# DCS.net
KiCad netlist of a schematic drawn in EAGLE
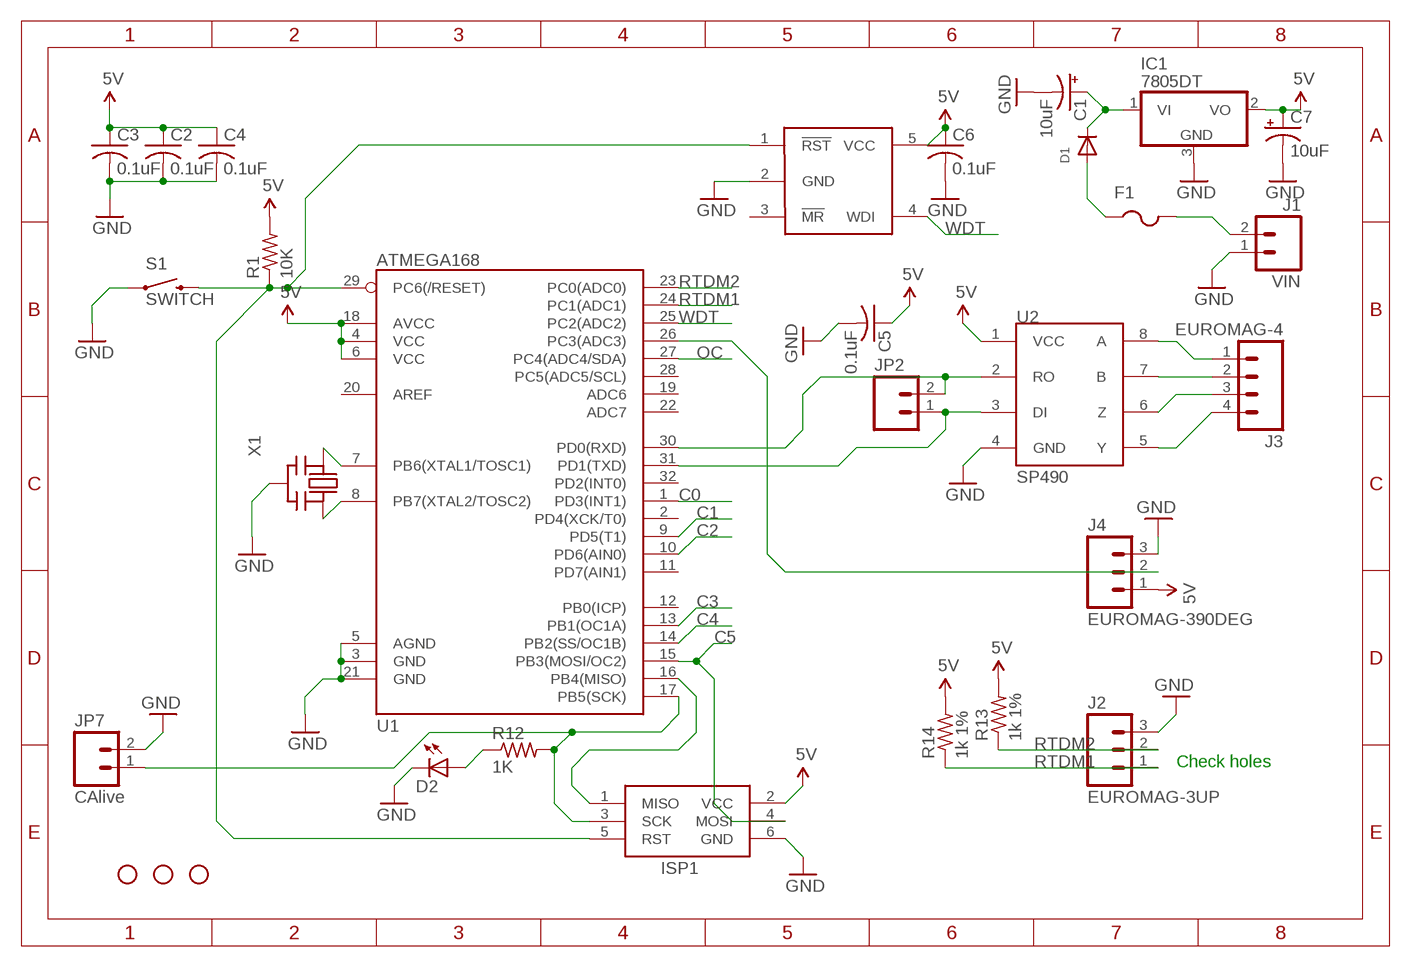
[diagram p0: schematic, sheet 1]
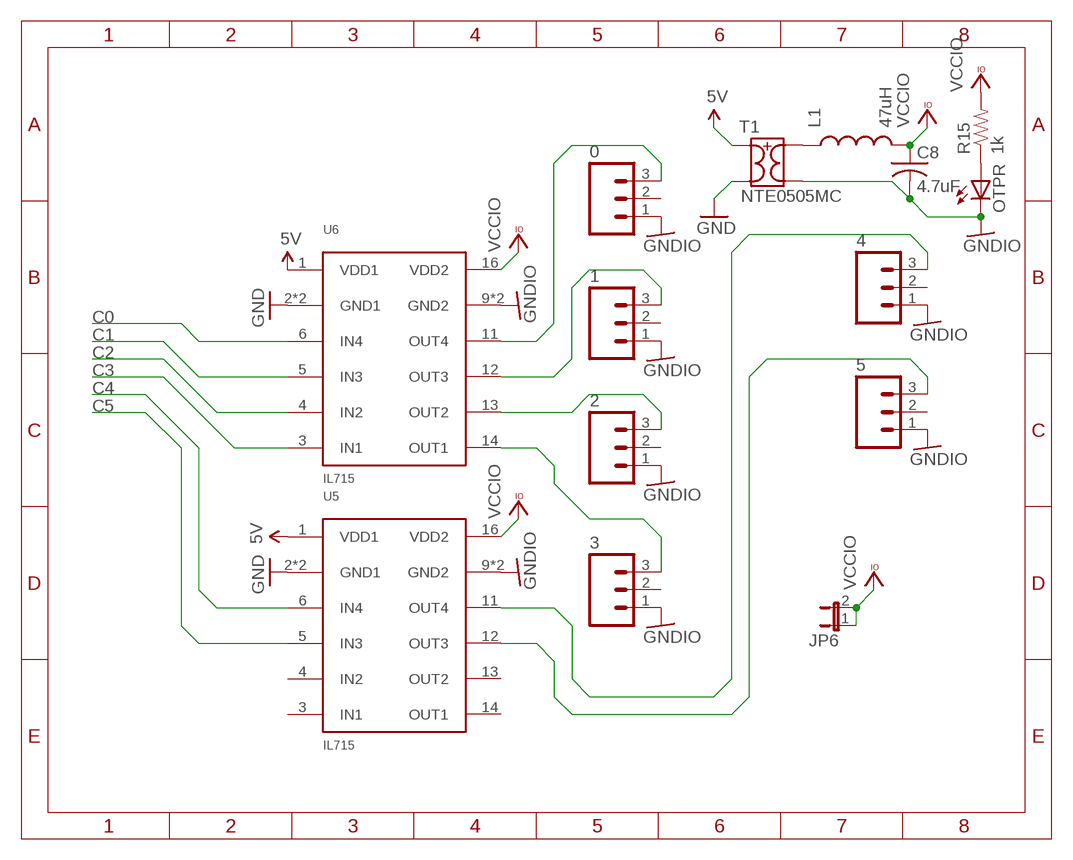
[diagram p1: schematic, sheet 2]
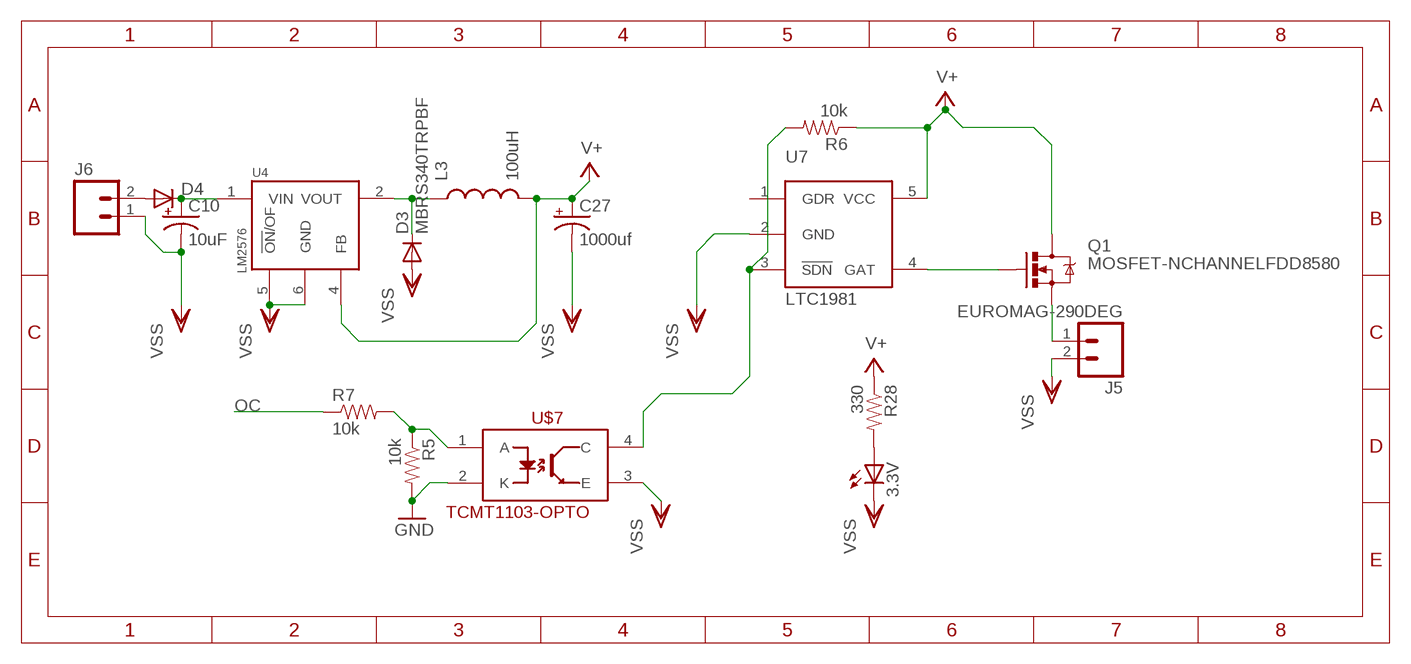
[diagram p2: schematic, sheet 3]

(export (version "E")
  (design (tool "Eeschema 10.0.6"))
  (components
    (comp (ref "C1")
      (value "10uF")
      (footprint "eagle-import:CT6032")
      (libsource (lib "eagle-import") (part "CPOL-USCT6032"))
    )
    (comp (ref "C2")
      (value "0.1uF")
      (footprint "eagle-import:C0805")
      (libsource (lib "eagle-import") (part "C-USC0805"))
    )
    (comp (ref "C3")
      (value "0.1uF")
      (footprint "eagle-import:C0805")
      (libsource (lib "eagle-import") (part "C-USC0805"))
    )
    (comp (ref "C4")
      (value "0.1uF")
      (footprint "eagle-import:C0805")
      (libsource (lib "eagle-import") (part "C-USC0805"))
    )
    (comp (ref "C5")
      (value "0.1uF")
      (footprint "eagle-import:C0805")
      (libsource (lib "eagle-import") (part "C-USC0805"))
    )
    (comp (ref "C6")
      (value "0.1uF")
      (footprint "eagle-import:C0805")
      (libsource (lib "eagle-import") (part "C-USC0805"))
    )
    (comp (ref "C7")
      (value "10uF")
      (footprint "eagle-import:CT3216")
      (libsource (lib "eagle-import") (part "CPOL-USCT3216"))
    )
    (comp (ref "D1")
      (value "DIODESMA")
      (footprint "eagle-import:SMADIODE")
      (libsource (lib "eagle-import") (part "adafruit_DIODESMA"))
    )
    (comp (ref "D2")
      (value "LEDCHIPLED_0805")
      (footprint "eagle-import:CHIPLED_0805")
      (libsource (lib "eagle-import") (part "LEDCHIPLED_0805"))
    )
    (comp (ref "F1")
      (value "PTCFUSE-1206")
      (footprint "eagle-import:R1206")
      (libsource (lib "eagle-import") (part "PTCFUSE-1206"))
    )
    (comp (ref "IC1")
      (value "7805DT")
      (footprint "eagle-import:TO252")
      (libsource (lib "eagle-import") (part "78DT05"))
    )
    (comp (ref "ISP1")
      (value "AVRISP-6")
      (footprint "eagle-import:AVRISP")
      (libsource (lib "eagle-import") (part "AVRISP-6"))
    )
    (comp (ref "J1")
      (value "VIN")
      (footprint "eagle-import:M2")
      (libsource (lib "eagle-import") (part "EUROMAG-290DEG"))
    )
    (comp (ref "J2")
      (value "EUROMAG-3UP")
      (footprint "eagle-import:M3-UP")
      (libsource (lib "eagle-import") (part "EUROMAG-3UP"))
    )
    (comp (ref "J3")
      (value "EUROMAG-4")
      (footprint "eagle-import:M4")
      (libsource (lib "eagle-import") (part "EUROMAG-4"))
    )
    (comp (ref "J4")
      (value "EUROMAG-390DEG")
      (footprint "eagle-import:M3")
      (libsource (lib "eagle-import") (part "EUROMAG-390DEG"))
    )
    (comp (ref "JP1")
      (value "STAND-OFF")
      (footprint "eagle-import:STAND-OFF")
      (libsource (lib "eagle-import") (part "STAND-OFF"))
    )
    (comp (ref "JP2")
      (value "M02LOCK")
      (footprint "eagle-import:1X02_LOCK")
      (libsource (lib "eagle-import") (part "M02LOCK"))
    )
    (comp (ref "JP3")
      (value "STAND-OFF")
      (footprint "eagle-import:STAND-OFF")
      (libsource (lib "eagle-import") (part "STAND-OFF"))
    )
    (comp (ref "JP5")
      (value "STAND-OFF")
      (footprint "eagle-import:STAND-OFF")
      (libsource (lib "eagle-import") (part "STAND-OFF"))
    )
    (comp (ref "JP7")
      (value "CAlive")
      (footprint "eagle-import:MOLEX-1X2_LOCK")
      (libsource (lib "eagle-import") (part "M02POLAR_LOCK"))
    )
    (comp (ref "R1")
      (value "10K")
      (footprint "eagle-import:M0805")
      (libsource (lib "eagle-import") (part "R-US_M0805"))
    )
    (comp (ref "R12")
      (value "1K")
      (footprint "eagle-import:M0805")
      (libsource (lib "eagle-import") (part "R-US_M0805"))
    )
    (comp (ref "R13")
      (value "1k 1%")
      (footprint "eagle-import:M0805")
      (libsource (lib "eagle-import") (part "R-US_M0805"))
    )
    (comp (ref "R14")
      (value "1k 1%")
      (footprint "eagle-import:M0805")
      (libsource (lib "eagle-import") (part "R-US_M0805"))
    )
    (comp (ref "S1")
      (value "SWITCH")
      (footprint "eagle-import:TACTILE-PTH")
      (libsource (lib "eagle-import") (part "SWITCH-MOMENTARY-2PTH"))
    )
    (comp (ref "U1")
      (value "ATMEGA168")
      (footprint "eagle-import:TQFP32-08")
      (libsource (lib "eagle-import") (part "ATMEGA168"))
    )
    (comp (ref "U2")
      (value "SP490")
      (footprint "eagle-import:SO08")
      (libsource (lib "eagle-import") (part "ISL83077"))
    )
    (comp (ref "U3")
      (value "MAX823")
      (footprint "eagle-import:SOT23-5L")
      (libsource (lib "eagle-import") (part "MAX823"))
    )
    (comp (ref "X1")
      (value "CERMOSCILL-AWCSR")
      (footprint "eagle-import:AWCSR")
      (libsource (lib "eagle-import") (part "CERMOSCILL-AWCSR"))
    )
    (comp (ref "0")
      (value "M03PTH")
      (footprint "eagle-import:1X03")
      (libsource (lib "eagle-import") (part "M03PTH"))
    )
    (comp (ref "1")
      (value "M03PTH")
      (footprint "eagle-import:1X03")
      (libsource (lib "eagle-import") (part "M03PTH"))
    )
    (comp (ref "2")
      (value "M03PTH")
      (footprint "eagle-import:1X03")
      (libsource (lib "eagle-import") (part "M03PTH"))
    )
    (comp (ref "3")
      (value "M03PTH")
      (footprint "eagle-import:1X03")
      (libsource (lib "eagle-import") (part "M03PTH"))
    )
    (comp (ref "4")
      (value "M03PTH")
      (footprint "eagle-import:1X03")
      (libsource (lib "eagle-import") (part "M03PTH"))
    )
    (comp (ref "5")
      (value "M03PTH")
      (footprint "eagle-import:1X03")
      (libsource (lib "eagle-import") (part "M03PTH"))
    )
    (comp (ref "C8")
      (value "4.7uF")
      (footprint "eagle-import:C0805")
      (libsource (lib "eagle-import") (part "C-USC0805"))
    )
    (comp (ref "JP6")
      (value "JUMPER-2SMD-NO")
      (footprint "eagle-import:SJ_2S-NO")
      (libsource (lib "eagle-import") (part "JUMPER-2SMD-NO"))
    )
    (comp (ref "L1")
      (value "47uH")
      (footprint "eagle-import:0805")
      (libsource (lib "eagle-import") (part "INDUCTOR1"))
    )
    (comp (ref "OTPR")
      (value "LEDCHIP-LED0805")
      (footprint "eagle-import:CHIP-LED0805")
      (libsource (lib "eagle-import") (part "LEDCHIP-LED0805"))
    )
    (comp (ref "R15")
      (value "1k")
      (footprint "eagle-import:0805")
      (libsource (lib "eagle-import") (part "RESISTOR0805-RES"))
    )
    (comp (ref "T1")
      (value "NTE0505MC")
      (footprint "eagle-import:SO-8FT")
      (libsource (lib "eagle-import") (part "NTE0505MC"))
    )
    (comp (ref "U5")
      (value "IL715")
      (footprint "eagle-import:S016")
      (libsource (lib "eagle-import") (part "IL715"))
    )
    (comp (ref "U6")
      (value "IL715")
      (footprint "eagle-import:S016")
      (libsource (lib "eagle-import") (part "IL715"))
    )
    (comp (ref "3.3V")
      (value "LEDCHIPLED_0805")
      (footprint "eagle-import:CHIPLED_0805")
      (libsource (lib "eagle-import") (part "LEDCHIPLED_0805"))
    )
    (comp (ref "C10")
      (value "10uF")
      (footprint "eagle-import:EIA7343")
      (libsource (lib "eagle-import") (part "CAP_POL7343"))
    )
    (comp (ref "C27")
      (value "1000uf")
      (footprint "eagle-import:PANASONIC_G")
      (libsource (lib "eagle-import") (part "CAP_POLG"))
    )
    (comp (ref "D3")
      (value "MBRS340TRPBF")
      (footprint "eagle-import:SMC")
      (libsource (lib "eagle-import") (part "DIODE-SMC"))
    )
    (comp (ref "D4")
      (value "DIODESMB")
      (footprint "eagle-import:SMB-DIODE")
      (libsource (lib "eagle-import") (part "DIODESMB"))
    )
    (comp (ref "J5")
      (value "EUROMAG-290DEG")
      (footprint "eagle-import:M2")
      (libsource (lib "eagle-import") (part "EUROMAG-290DEG"))
    )
    (comp (ref "J6")
      (value "EUROMAG-290DEG")
      (footprint "eagle-import:M2")
      (libsource (lib "eagle-import") (part "EUROMAG-290DEG"))
    )
    (comp (ref "L3")
      (value "100uH")
      (footprint "eagle-import:INDUCTOR_5X3")
      (libsource (lib "eagle-import") (part "INDUCTOR"))
    )
    (comp (ref "Q1")
      (value "MOSFET-NCHANNELFDD8580")
      (footprint "eagle-import:DPAK")
      (libsource (lib "eagle-import") (part "MOSFET-NCHANNELFDD8580"))
    )
    (comp (ref "R5")
      (value "10k")
      (footprint "eagle-import:0805")
      (libsource (lib "eagle-import") (part "RESISTOR0805-RES"))
    )
    (comp (ref "R6")
      (value "10k")
      (footprint "eagle-import:0805")
      (libsource (lib "eagle-import") (part "RESISTOR0805-RES"))
    )
    (comp (ref "R7")
      (value "10k")
      (footprint "eagle-import:0805")
      (libsource (lib "eagle-import") (part "RESISTOR0805-RES"))
    )
    (comp (ref "R28")
      (value "330")
      (footprint "eagle-import:0805")
      (libsource (lib "eagle-import") (part "RESISTOR0805-RES"))
    )
    (comp (ref "U$7")
      (value "TCMT1103-OPTO")
      (footprint "eagle-import:SSOP-4")
      (libsource (lib "eagle-import") (part "TCMT1103-OPTO"))
    )
    (comp (ref "U4")
      (value "LM2576")
      (footprint "eagle-import:TO-263-5")
      (libsource (lib "eagle-import") (part "LM2576"))
    )
    (comp (ref "U7")
      (value "LTC1981")
      (footprint "eagle-import:SOT23-5L")
      (libsource (lib "eagle-import") (part "LTC1981"))
    )
  )
  (nets
    (net (code "1") (name "5V") (class "Default")
      (node (ref "C2") (pin "1") (pinfunction "1_1") (pintype "passive"))
      (node (ref "C3") (pin "1") (pinfunction "1_1") (pintype "passive"))
      (node (ref "C4") (pin "1") (pinfunction "1_1") (pintype "passive"))
      (node (ref "C5") (pin "1") (pinfunction "1_1") (pintype "passive"))
      (node (ref "C6") (pin "1") (pinfunction "1_1") (pintype "passive"))
      (node (ref "C7") (pin "+") (pinfunction "+_+") (pintype "passive"))
      (node (ref "IC1") (pin "2") (pinfunction "VO_2") (pintype "passive"))
      (node (ref "ISP1") (pin "2") (pinfunction "VCC_2") (pintype "power_in"))
      (node (ref "J4") (pin "1") (pinfunction "1_1") (pintype "passive"))
      (node (ref "R1") (pin "2") (pinfunction "2_2") (pintype "passive"))
      (node (ref "R13") (pin "2") (pinfunction "2_2") (pintype "passive"))
      (node (ref "R14") (pin "2") (pinfunction "2_2") (pintype "passive"))
      (node (ref "T1") (pin "3") (pinfunction "1_3") (pintype "passive"))
      (node (ref "U1") (pin "18") (pinfunction "AVCC_18") (pintype "bidirectional"))
      (node (ref "U1") (pin "4") (pinfunction "VCC_4") (pintype "bidirectional"))
      (node (ref "U1") (pin "6") (pinfunction "VCC_6") (pintype "bidirectional"))
      (node (ref "U2") (pin "1") (pinfunction "VCC_1") (pintype "bidirectional"))
      (node (ref "U3") (pin "5") (pinfunction "VCC_5") (pintype "bidirectional"))
      (node (ref "U5") (pin "1") (pinfunction "VDD1_1") (pintype "bidirectional"))
      (node (ref "U6") (pin "1") (pinfunction "VDD1_1") (pintype "bidirectional"))
    )
    (net (code "2") (name "C0") (class "Default")
      (node (ref "U1") (pin "1") (pinfunction "PD3(INT1)_1") (pintype "bidirectional"))
      (node (ref "U6") (pin "6") (pinfunction "IN4_6") (pintype "bidirectional"))
    )
    (net (code "3") (name "C1") (class "Default")
      (node (ref "U1") (pin "9") (pinfunction "PD5(T1)_9") (pintype "bidirectional"))
      (node (ref "U6") (pin "5") (pinfunction "IN3_5") (pintype "bidirectional"))
    )
    (net (code "4") (name "C2") (class "Default")
      (node (ref "U1") (pin "10") (pinfunction "PD6(AIN0)_10") (pintype "bidirectional"))
      (node (ref "U6") (pin "4") (pinfunction "IN2_4") (pintype "bidirectional"))
    )
    (net (code "5") (name "C3") (class "Default")
      (node (ref "U1") (pin "13") (pinfunction "PB1(OC1A)_13") (pintype "bidirectional"))
      (node (ref "U6") (pin "3") (pinfunction "IN1_3") (pintype "bidirectional"))
    )
    (net (code "6") (name "C4") (class "Default")
      (node (ref "U1") (pin "14") (pinfunction "PB2(SS/OC1B)_14") (pintype "bidirectional"))
      (node (ref "U5") (pin "6") (pinfunction "IN4_6") (pintype "bidirectional"))
    )
    (net (code "7") (name "C5") (class "Default")
      (node (ref "ISP1") (pin "4") (pinfunction "MOSI_4") (pintype "output"))
      (node (ref "U1") (pin "15") (pinfunction "PB3(MOSI/OC2)_15") (pintype "bidirectional"))
      (node (ref "U5") (pin "5") (pinfunction "IN3_5") (pintype "bidirectional"))
    )
    (net (code "8") (name "GND") (class "Default")
      (node (ref "C1") (pin "-") (pinfunction "-_-") (pintype "passive"))
      (node (ref "C2") (pin "2") (pinfunction "2_2") (pintype "passive"))
      (node (ref "C3") (pin "2") (pinfunction "2_2") (pintype "passive"))
      (node (ref "C4") (pin "2") (pinfunction "2_2") (pintype "passive"))
      (node (ref "C5") (pin "2") (pinfunction "2_2") (pintype "passive"))
      (node (ref "C6") (pin "2") (pinfunction "2_2") (pintype "passive"))
      (node (ref "C7") (pin "-") (pinfunction "-_-") (pintype "passive"))
      (node (ref "D2") (pin "C") (pinfunction "C_C") (pintype "passive"))
      (node (ref "IC1") (pin "3") (pinfunction "GND_3") (pintype "passive"))
      (node (ref "ISP1") (pin "6") (pinfunction "GND_6") (pintype "power_in"))
      (node (ref "J1") (pin "1") (pinfunction "1_1") (pintype "passive"))
      (node (ref "J2") (pin "3") (pinfunction "3_3") (pintype "passive"))
      (node (ref "J4") (pin "3") (pinfunction "3_3") (pintype "passive"))
      (node (ref "JP7") (pin "2") (pinfunction "2_2") (pintype "passive"))
      (node (ref "R5") (pin "2") (pinfunction "2_2") (pintype "passive"))
      (node (ref "S1") (pin "1") (pinfunction "1_1") (pintype "passive"))
      (node (ref "T1") (pin "1") (pinfunction "2_1") (pintype "passive"))
      (node (ref "U$7") (pin "2") (pinfunction "K_2") (pintype "bidirectional"))
      (node (ref "U1") (pin "21") (pinfunction "GND_21") (pintype "bidirectional"))
      (node (ref "U1") (pin "3") (pinfunction "GND_3") (pintype "bidirectional"))
      (node (ref "U1") (pin "5") (pinfunction "AGND_5") (pintype "bidirectional"))
      (node (ref "U2") (pin "4") (pinfunction "GND_4") (pintype "bidirectional"))
      (node (ref "U3") (pin "2") (pinfunction "GND_2") (pintype "bidirectional"))
      (node (ref "U5") (pin "2") (pinfunction "GND1_2") (pintype "bidirectional"))
      (node (ref "U5") (pin "8") (pinfunction "GND1_8") (pintype "bidirectional"))
      (node (ref "U6") (pin "2") (pinfunction "GND1_2") (pintype "bidirectional"))
      (node (ref "U6") (pin "8") (pinfunction "GND1_8") (pintype "bidirectional"))
      (node (ref "X1") (pin "2") (pinfunction "GND_2") (pintype "bidirectional"))
    )
    (net (code "9") (name "GNDIO") (class "Default")
      (node (ref "0") (pin "1") (pinfunction "1_1") (pintype "passive"))
      (node (ref "1") (pin "1") (pinfunction "1_1") (pintype "passive"))
      (node (ref "2") (pin "1") (pinfunction "1_1") (pintype "passive"))
      (node (ref "3") (pin "1") (pinfunction "1_1") (pintype "passive"))
      (node (ref "4") (pin "1") (pinfunction "1_1") (pintype "passive"))
      (node (ref "5") (pin "1") (pinfunction "1_1") (pintype "passive"))
      (node (ref "C8") (pin "2") (pinfunction "2_2") (pintype "passive"))
      (node (ref "OTPR") (pin "C") (pinfunction "C_C") (pintype "passive"))
      (node (ref "T1") (pin "7") (pinfunction "3_7") (pintype "passive"))
      (node (ref "U5") (pin "15") (pinfunction "GND2_15") (pintype "bidirectional"))
      (node (ref "U5") (pin "9") (pinfunction "GND2_9") (pintype "bidirectional"))
      (node (ref "U6") (pin "15") (pinfunction "GND2_15") (pintype "bidirectional"))
      (node (ref "U6") (pin "9") (pinfunction "GND2_9") (pintype "bidirectional"))
    )
    (net (code "10") (name "Net-(3.3V-PadA)") (class "Default")
      (node (ref "3.3V") (pin "A") (pinfunction "A_A") (pintype "passive"))
      (node (ref "R28") (pin "2") (pinfunction "2_2") (pintype "passive"))
    )
    (net (code "11") (name "Net-(C10-+)") (class "Default")
      (node (ref "C10") (pin "A") (pinfunction "+_A") (pintype "passive"))
      (node (ref "D4") (pin "C") (pinfunction "C_C") (pintype "passive"))
      (node (ref "U4") (pin "1") (pinfunction "VIN_1") (pintype "power_in"))
    )
    (net (code "12") (name "Net-(D1-PadA)") (class "Default")
      (node (ref "D1") (pin "A") (pinfunction "A_A") (pintype "passive"))
      (node (ref "F1") (pin "1") (pinfunction "1_1") (pintype "passive"))
    )
    (net (code "13") (name "Net-(D2-PadA)") (class "Default")
      (node (ref "D2") (pin "A") (pinfunction "A_A") (pintype "passive"))
      (node (ref "R12") (pin "1") (pinfunction "1_1") (pintype "passive"))
    )
    (net (code "14") (name "Net-(D4-PadA)") (class "Default")
      (node (ref "D4") (pin "A") (pinfunction "A_A") (pintype "passive"))
      (node (ref "J6") (pin "2") (pinfunction "2_2") (pintype "passive"))
    )
    (net (code "15") (name "Net-(F1-Pad2)") (class "Default")
      (node (ref "F1") (pin "2") (pinfunction "2_2") (pintype "passive"))
      (node (ref "J1") (pin "2") (pinfunction "2_2") (pintype "passive"))
    )
    (net (code "16") (name "Net-(IC1-VI)") (class "Default")
      (node (ref "C1") (pin "+") (pinfunction "+_+") (pintype "passive"))
      (node (ref "D1") (pin "C") (pinfunction "C_C") (pintype "passive"))
      (node (ref "IC1") (pin "1") (pinfunction "VI_1") (pintype "input"))
    )
    (net (code "17") (name "Net-(ISP1-MISO)") (class "Default")
      (node (ref "ISP1") (pin "1") (pinfunction "MISO_1") (pintype "input"))
      (node (ref "U1") (pin "16") (pinfunction "PB4(MISO)_16") (pintype "bidirectional"))
    )
    (net (code "18") (name "Net-(ISP1-RST)") (class "Default")
      (node (ref "ISP1") (pin "5") (pinfunction "RST_5") (pintype "output"))
      (node (ref "R1") (pin "1") (pinfunction "1_1") (pintype "passive"))
      (node (ref "S1") (pin "3") (pinfunction "2_3") (pintype "passive"))
      (node (ref "U1") (pin "29") (pinfunction "PC6(/RESET)_29") (pintype "bidirectional"))
      (node (ref "U3") (pin "1") (pinfunction "~{RST}_1") (pintype "bidirectional"))
    )
    (net (code "19") (name "Net-(ISP1-SCK)") (class "Default")
      (node (ref "ISP1") (pin "3") (pinfunction "SCK_3") (pintype "output"))
      (node (ref "JP7") (pin "1") (pinfunction "1_1") (pintype "passive"))
      (node (ref "R12") (pin "2") (pinfunction "2_2") (pintype "passive"))
      (node (ref "U1") (pin "17") (pinfunction "PB5(SCK)_17") (pintype "bidirectional"))
    )
    (net (code "20") (name "Net-(OTPR-PadA)") (class "Default")
      (node (ref "OTPR") (pin "A") (pinfunction "A_A") (pintype "passive"))
      (node (ref "R15") (pin "1") (pinfunction "1_1") (pintype "passive"))
    )
    (net (code "21") (name "Net-(Q1-G)") (class "Default")
      (node (ref "Q1") (pin "1") (pinfunction "G_1") (pintype "passive"))
      (node (ref "U7") (pin "4") (pinfunction "GAT_4") (pintype "bidirectional"))
    )
    (net (code "22") (name "Net-(Q1-S)") (class "Default")
      (node (ref "J5") (pin "1") (pinfunction "1_1") (pintype "passive"))
      (node (ref "Q1") (pin "3") (pinfunction "S_3") (pintype "passive"))
    )
    (net (code "23") (name "Net-(T1-4)") (class "Default")
      (node (ref "L1") (pin "1") (pinfunction "1_1") (pintype "passive"))
      (node (ref "T1") (pin "8") (pinfunction "4_8") (pintype "passive"))
    )
    (net (code "24") (name "Net-(U$7-A)") (class "Default")
      (node (ref "R5") (pin "1") (pinfunction "1_1") (pintype "passive"))
      (node (ref "R7") (pin "2") (pinfunction "2_2") (pintype "passive"))
      (node (ref "U$7") (pin "1") (pinfunction "A_1") (pintype "bidirectional"))
    )
    (net (code "25") (name "Net-(U$7-C)") (class "Default")
      (node (ref "R6") (pin "2") (pinfunction "2_2") (pintype "passive"))
      (node (ref "U$7") (pin "4") (pinfunction "C_4") (pintype "bidirectional"))
      (node (ref "U7") (pin "3") (pinfunction "~{SDN}_3") (pintype "bidirectional"))
    )
    (net (code "26") (name "Net-(U1-PB6(XTAL1{slash}TOSC1))") (class "Default")
      (node (ref "U1") (pin "7") (pinfunction "PB6(XTAL1/TOSC1)_7") (pintype "bidirectional"))
      (node (ref "X1") (pin "1") (pinfunction "IN_1") (pintype "bidirectional"))
    )
    (net (code "27") (name "Net-(U1-PB7(XTAL2{slash}TOSC2))") (class "Default")
      (node (ref "U1") (pin "8") (pinfunction "PB7(XTAL2/TOSC2)_8") (pintype "bidirectional"))
      (node (ref "X1") (pin "3") (pinfunction "OUT_3") (pintype "bidirectional"))
    )
    (net (code "28") (name "Net-(U1-PC3(ADC3))") (class "Default")
      (node (ref "J4") (pin "2") (pinfunction "2_2") (pintype "passive"))
      (node (ref "U1") (pin "26") (pinfunction "PC3(ADC3)_26") (pintype "bidirectional"))
    )
    (net (code "29") (name "Net-(U1-PD0(RXD))") (class "Default")
      (node (ref "JP2") (pin "2") (pinfunction "2_2") (pintype "passive"))
      (node (ref "U1") (pin "30") (pinfunction "PD0(RXD)_30") (pintype "bidirectional"))
      (node (ref "U2") (pin "2") (pinfunction "RO_2") (pintype "bidirectional"))
    )
    (net (code "30") (name "Net-(U1-PD1(TXD))") (class "Default")
      (node (ref "JP2") (pin "1") (pinfunction "1_1") (pintype "passive"))
      (node (ref "U1") (pin "31") (pinfunction "PD1(TXD)_31") (pintype "bidirectional"))
      (node (ref "U2") (pin "3") (pinfunction "DI_3") (pintype "bidirectional"))
    )
    (net (code "31") (name "Net-(U2-A)") (class "Default")
      (node (ref "J3") (pin "1") (pinfunction "1_1") (pintype "passive"))
      (node (ref "U2") (pin "8") (pinfunction "A_8") (pintype "bidirectional"))
    )
    (net (code "32") (name "Net-(U2-B)") (class "Default")
      (node (ref "J3") (pin "2") (pinfunction "2_2") (pintype "passive"))
      (node (ref "U2") (pin "7") (pinfunction "B_7") (pintype "bidirectional"))
    )
    (net (code "33") (name "Net-(U2-Y)") (class "Default")
      (node (ref "J3") (pin "4") (pinfunction "4_4") (pintype "passive"))
      (node (ref "U2") (pin "5") (pinfunction "Y_5") (pintype "bidirectional"))
    )
    (net (code "34") (name "Net-(U2-Z)") (class "Default")
      (node (ref "J3") (pin "3") (pinfunction "3_3") (pintype "passive"))
      (node (ref "U2") (pin "6") (pinfunction "Z_6") (pintype "bidirectional"))
    )
    (net (code "35") (name "Net-(U4-VOUT)") (class "Default")
      (node (ref "D3") (pin "C") (pinfunction "C_C") (pintype "passive"))
      (node (ref "L3") (pin "1") (pinfunction "1_1") (pintype "passive"))
      (node (ref "U4") (pin "2") (pinfunction "VOUT_2") (pintype "power_in"))
    )
    (net (code "36") (name "Net-(U5-OUT3)") (class "Default")
      (node (ref "5") (pin "3") (pinfunction "3_3") (pintype "passive"))
      (node (ref "U5") (pin "12") (pinfunction "OUT3_12") (pintype "bidirectional"))
    )
    (net (code "37") (name "Net-(U5-OUT4)") (class "Default")
      (node (ref "4") (pin "3") (pinfunction "3_3") (pintype "passive"))
      (node (ref "U5") (pin "11") (pinfunction "OUT4_11") (pintype "bidirectional"))
    )
    (net (code "38") (name "Net-(U6-OUT1)") (class "Default")
      (node (ref "3") (pin "3") (pinfunction "3_3") (pintype "passive"))
      (node (ref "U6") (pin "14") (pinfunction "OUT1_14") (pintype "bidirectional"))
    )
    (net (code "39") (name "Net-(U6-OUT2)") (class "Default")
      (node (ref "2") (pin "3") (pinfunction "3_3") (pintype "passive"))
      (node (ref "U6") (pin "13") (pinfunction "OUT2_13") (pintype "bidirectional"))
    )
    (net (code "40") (name "Net-(U6-OUT3)") (class "Default")
      (node (ref "1") (pin "3") (pinfunction "3_3") (pintype "passive"))
      (node (ref "U6") (pin "12") (pinfunction "OUT3_12") (pintype "bidirectional"))
    )
    (net (code "41") (name "Net-(U6-OUT4)") (class "Default")
      (node (ref "0") (pin "3") (pinfunction "3_3") (pintype "passive"))
      (node (ref "U6") (pin "11") (pinfunction "OUT4_11") (pintype "bidirectional"))
    )
    (net (code "42") (name "OC") (class "Default")
      (node (ref "R7") (pin "1") (pinfunction "1_1") (pintype "passive"))
      (node (ref "U1") (pin "27") (pinfunction "PC4(ADC4/SDA)_27") (pintype "bidirectional"))
    )
    (net (code "43") (name "RTDM1") (class "Default")
      (node (ref "J2") (pin "1") (pinfunction "1_1") (pintype "passive"))
      (node (ref "R14") (pin "1") (pinfunction "1_1") (pintype "passive"))
      (node (ref "U1") (pin "24") (pinfunction "PC1(ADC1)_24") (pintype "bidirectional"))
    )
    (net (code "44") (name "RTDM2") (class "Default")
      (node (ref "J2") (pin "2") (pinfunction "2_2") (pintype "passive"))
      (node (ref "R13") (pin "1") (pinfunction "1_1") (pintype "passive"))
      (node (ref "U1") (pin "23") (pinfunction "PC0(ADC0)_23") (pintype "bidirectional"))
    )
    (net (code "45") (name "V+") (class "Default")
      (node (ref "C27") (pin "+") (pinfunction "+_+") (pintype "passive"))
      (node (ref "L3") (pin "2") (pinfunction "2_2") (pintype "passive"))
      (node (ref "Q1") (pin "4") (pinfunction "D_4") (pintype "passive"))
      (node (ref "R28") (pin "1") (pinfunction "1_1") (pintype "passive"))
      (node (ref "R6") (pin "1") (pinfunction "1_1") (pintype "passive"))
      (node (ref "U4") (pin "4") (pinfunction "FB_4") (pintype "power_in"))
      (node (ref "U7") (pin "5") (pinfunction "VCC_5") (pintype "bidirectional"))
    )
    (net (code "46") (name "VCCIO") (class "Default")
      (node (ref "C8") (pin "1") (pinfunction "1_1") (pintype "passive"))
      (node (ref "JP6") (pin "1") (pinfunction "1_1") (pintype "passive"))
      (node (ref "JP6") (pin "2") (pinfunction "2_2") (pintype "passive"))
      (node (ref "L1") (pin "2") (pinfunction "2_2") (pintype "passive"))
      (node (ref "R15") (pin "2") (pinfunction "2_2") (pintype "passive"))
      (node (ref "U5") (pin "16") (pinfunction "VDD2_16") (pintype "bidirectional"))
      (node (ref "U6") (pin "16") (pinfunction "VDD2_16") (pintype "bidirectional"))
    )
    (net (code "47") (name "VSS") (class "Default")
      (node (ref "3.3V") (pin "C") (pinfunction "C_C") (pintype "passive"))
      (node (ref "C10") (pin "C") (pinfunction "-_C") (pintype "passive"))
      (node (ref "C27") (pin "-") (pinfunction "-_-") (pintype "passive"))
      (node (ref "D3") (pin "A") (pinfunction "A_A") (pintype "passive"))
      (node (ref "J5") (pin "2") (pinfunction "2_2") (pintype "passive"))
      (node (ref "J6") (pin "1") (pinfunction "1_1") (pintype "passive"))
      (node (ref "U$7") (pin "3") (pinfunction "E_3") (pintype "bidirectional"))
      (node (ref "U4") (pin "5") (pinfunction "~{ON}/OF_5") (pintype "bidirectional"))
      (node (ref "U4") (pin "6") (pinfunction "GND_6") (pintype "power_in"))
      (node (ref "U7") (pin "2") (pinfunction "GND_2") (pintype "bidirectional"))
    )
    (net (code "48") (name "WDT") (class "Default")
      (node (ref "U1") (pin "25") (pinfunction "PC2(ADC2)_25") (pintype "bidirectional"))
      (node (ref "U3") (pin "4") (pinfunction "WDI_4") (pintype "bidirectional"))
    )
    (net (code "49") (name "unconnected-(0-Pad2)") (class "Default")
      (node (ref "0") (pin "2") (pinfunction "2_2") (pintype "passive"))
    )
    (net (code "50") (name "unconnected-(1-Pad2)") (class "Default")
      (node (ref "1") (pin "2") (pinfunction "2_2") (pintype "passive"))
    )
    (net (code "51") (name "unconnected-(2-Pad2)") (class "Default")
      (node (ref "2") (pin "2") (pinfunction "2_2") (pintype "passive"))
    )
    (net (code "52") (name "unconnected-(3-Pad2)") (class "Default")
      (node (ref "3") (pin "2") (pinfunction "2_2") (pintype "passive"))
    )
    (net (code "53") (name "unconnected-(4-Pad2)") (class "Default")
      (node (ref "4") (pin "2") (pinfunction "2_2") (pintype "passive"))
    )
    (net (code "54") (name "unconnected-(5-Pad2)") (class "Default")
      (node (ref "5") (pin "2") (pinfunction "2_2") (pintype "passive"))
    )
    (net (code "55") (name "unconnected-(U1-ADC6-Pad19)") (class "Default")
      (node (ref "U1") (pin "19") (pinfunction "ADC6_19") (pintype "bidirectional"))
    )
    (net (code "56") (name "unconnected-(U1-ADC7-Pad22)") (class "Default")
      (node (ref "U1") (pin "22") (pinfunction "ADC7_22") (pintype "bidirectional"))
    )
    (net (code "57") (name "unconnected-(U1-AREF-Pad20)") (class "Default")
      (node (ref "U1") (pin "20") (pinfunction "AREF_20") (pintype "bidirectional"))
    )
    (net (code "58") (name "unconnected-(U1-PB0(ICP)-Pad12)") (class "Default")
      (node (ref "U1") (pin "12") (pinfunction "PB0(ICP)_12") (pintype "bidirectional"))
    )
    (net (code "59") (name "unconnected-(U1-PC5(ADC5{slash}SCL)-Pad28)") (class "Default")
      (node (ref "U1") (pin "28") (pinfunction "PC5(ADC5/SCL)_28") (pintype "bidirectional"))
    )
    (net (code "60") (name "unconnected-(U1-PD2(INT0)-Pad32)") (class "Default")
      (node (ref "U1") (pin "32") (pinfunction "PD2(INT0)_32") (pintype "bidirectional"))
    )
    (net (code "61") (name "unconnected-(U1-PD4(XCK{slash}T0)-Pad2)") (class "Default")
      (node (ref "U1") (pin "2") (pinfunction "PD4(XCK/T0)_2") (pintype "bidirectional"))
    )
    (net (code "62") (name "unconnected-(U1-PD7(AIN1)-Pad11)") (class "Default")
      (node (ref "U1") (pin "11") (pinfunction "PD7(AIN1)_11") (pintype "bidirectional"))
    )
    (net (code "63") (name "unconnected-(U3-~{MR}-Pad3)") (class "Default")
      (node (ref "U3") (pin "3") (pinfunction "~{MR}_3") (pintype "bidirectional"))
    )
    (net (code "64") (name "unconnected-(U5-IN1-Pad3)") (class "Default")
      (node (ref "U5") (pin "3") (pinfunction "IN1_3") (pintype "bidirectional"))
    )
    (net (code "65") (name "unconnected-(U5-IN2-Pad4)") (class "Default")
      (node (ref "U5") (pin "4") (pinfunction "IN2_4") (pintype "bidirectional"))
    )
    (net (code "66") (name "unconnected-(U5-OUT1-Pad14)") (class "Default")
      (node (ref "U5") (pin "14") (pinfunction "OUT1_14") (pintype "bidirectional"))
    )
    (net (code "67") (name "unconnected-(U5-OUT2-Pad13)") (class "Default")
      (node (ref "U5") (pin "13") (pinfunction "OUT2_13") (pintype "bidirectional"))
    )
    (net (code "68") (name "unconnected-(U7-GDR-Pad1)") (class "Default")
      (node (ref "U7") (pin "1") (pinfunction "GDR_1") (pintype "bidirectional"))
    )
  )
)
